# attinier85-motherboard-mk-3_0.net
KiCad netlist of a schematic drawn in EAGLE
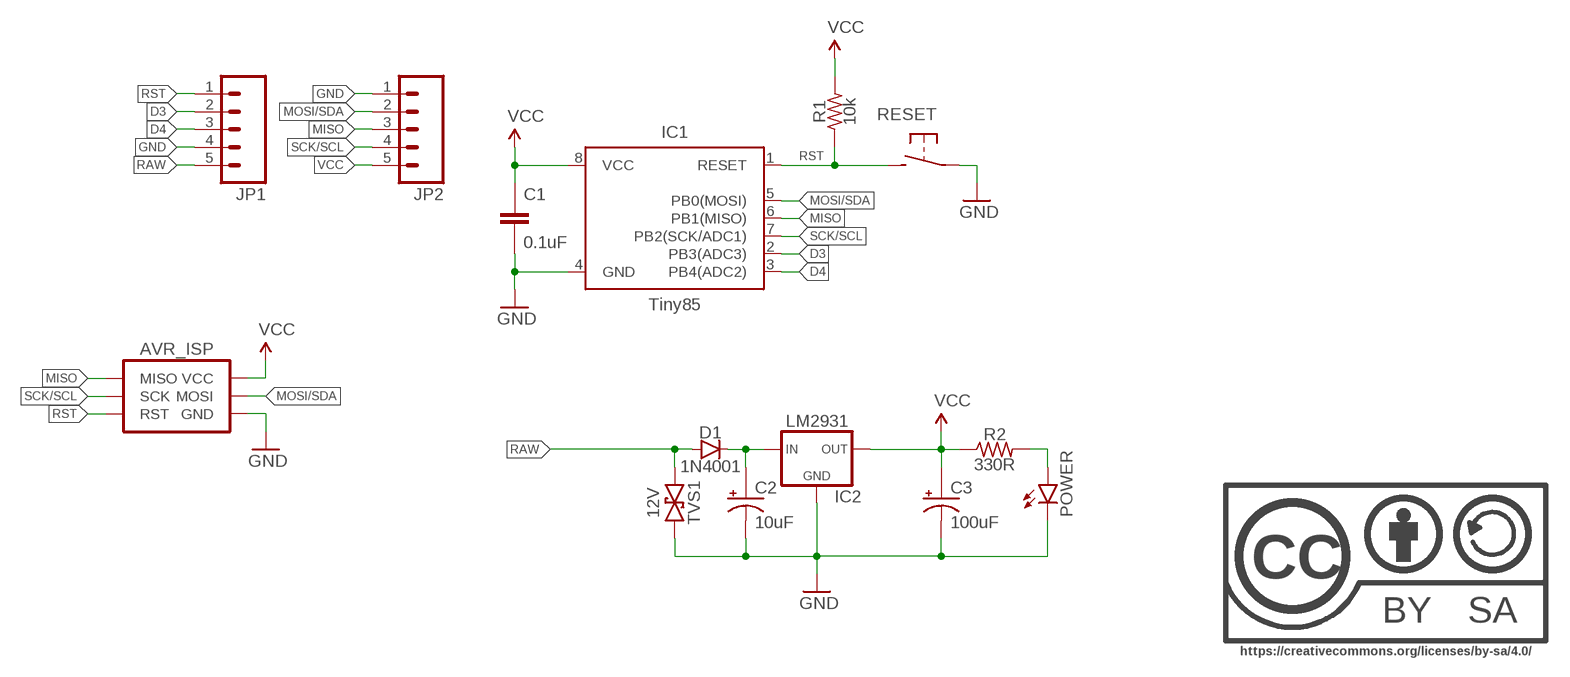
[diagram p0: schematic, sheet 1]

(export (version "E")
  (design (tool "Eeschema 10.0.6"))
  (components
    (comp (ref "AVR_ISP")
      (value "AVR_SPI_PRG_6PTH")
      (footprint "eagle-import:2X3")
      (libsource (lib "eagle-import") (part "AVR_SPI_PRG_6PTH"))
    )
    (comp (ref "C1")
      (value "0.1uF")
      (footprint "eagle-import:C025-024X044")
      (libsource (lib "eagle-import") (part "CAPACITOR-CERAMIC025-024X044"))
    )
    (comp (ref "C2")
      (value "10uF")
      (footprint "eagle-import:E2,5-5")
      (libsource (lib "eagle-import") (part "CAPACITOR-POLARIZEDE2.5-5"))
    )
    (comp (ref "C3")
      (value "100uF")
      (footprint "eagle-import:E2,5-5")
      (libsource (lib "eagle-import") (part "CAPACITOR-POLARIZEDE2.5-5"))
    )
    (comp (ref "D1")
      (value "1N4001")
      (footprint "eagle-import:DIODE-10.16MM")
      (libsource (lib "eagle-import") (part "DIODEPTH-10.68MM"))
    )
    (comp (ref "IC1")
      (value "Tiny85")
      (footprint "eagle-import:DIP08")
      (libsource (lib "eagle-import") (part "ATTINY45TINY85-20-DIP"))
    )
    (comp (ref "IC2")
      (value "LM2931")
      (footprint "eagle-import:TO-92-AMMO")
      (libsource (lib "eagle-import") (part "V_REG_78XXTO-92-INLINE"))
    )
    (comp (ref "JP1")
      (value "M05PTH")
      (footprint "eagle-import:1X05")
      (libsource (lib "eagle-import") (part "M05PTH"))
    )
    (comp (ref "JP2")
      (value "M05PTH")
      (footprint "eagle-import:1X05")
      (libsource (lib "eagle-import") (part "M05PTH"))
    )
    (comp (ref "POWER")
      (value "LED3MM-LESS")
      (footprint "eagle-import:LED3MM-LESSSILK")
      (libsource (lib "eagle-import") (part "LED3MM-LESS"))
    )
    (comp (ref "R1")
      (value "10k")
      (footprint "eagle-import:RESISTOR-AXIAL-PTH-7.62MM")
      (libsource (lib "eagle-import") (part "RESISTORPTH-AXIAL-7.62MM"))
    )
    (comp (ref "R2")
      (value "330R")
      (footprint "eagle-import:RESISTOR-AXIAL-PTH-7.62MM")
      (libsource (lib "eagle-import") (part "RESISTORPTH-AXIAL-7.62MM"))
    )
    (comp (ref "RESET")
      (value "DTS-6MM")
      (footprint "eagle-import:DTS-3-SMALL-PADS")
      (libsource (lib "eagle-import") (part "SPST-NO-TACT3MM-PTH-SMALL-PADS"))
    )
    (comp (ref "TVS1")
      (value "12V")
      (footprint "eagle-import:DO-41-TVS")
      (libsource (lib "eagle-import") (part "TVSDO-41-TVS-BIDIRECTIONAL"))
    )
    (comp (ref "U$1")
      (value "CC-BY-SA-4.0NO-URL")
      (footprint "eagle-import:CC-BY-SA-4.0-NO-URL")
      (libsource (lib "eagle-import") (part "CC-BY-SA-4.0NO-URL"))
    )
  )
  (nets
    (net (code "1") (name "D3") (class "Default")
      (node (ref "IC1") (pin "2") (pinfunction "PB3(ADC3)_2") (pintype "bidirectional"))
      (node (ref "JP1") (pin "2") (pinfunction "2_2") (pintype "passive"))
    )
    (net (code "2") (name "D4") (class "Default")
      (node (ref "IC1") (pin "3") (pinfunction "PB4(ADC2)_3") (pintype "bidirectional"))
      (node (ref "JP1") (pin "3") (pinfunction "3_3") (pintype "passive"))
    )
    (net (code "3") (name "GND") (class "Default")
      (node (ref "AVR_ISP") (pin "6") (pinfunction "GND_6") (pintype "passive"))
      (node (ref "C1") (pin "2") (pinfunction "2_2") (pintype "passive"))
      (node (ref "C2") (pin "-") (pinfunction "-_-") (pintype "passive"))
      (node (ref "C3") (pin "-") (pinfunction "-_-") (pintype "passive"))
      (node (ref "IC1") (pin "4") (pinfunction "GND_4") (pintype "bidirectional"))
      (node (ref "IC2") (pin "2") (pinfunction "GND_2") (pintype "bidirectional"))
      (node (ref "JP1") (pin "4") (pinfunction "4_4") (pintype "passive"))
      (node (ref "JP2") (pin "1") (pinfunction "1_1") (pintype "passive"))
      (node (ref "POWER") (pin "K") (pinfunction "C_K") (pintype "passive"))
      (node (ref "RESET") (pin "1") (pinfunction "1_1") (pintype "passive"))
      (node (ref "TVS1") (pin "P$2") (pinfunction "2_P$2") (pintype "passive"))
    )
    (net (code "4") (name "MISO") (class "Default")
      (node (ref "AVR_ISP") (pin "1") (pinfunction "MISO_1") (pintype "passive"))
      (node (ref "IC1") (pin "6") (pinfunction "PB1(MISO)_6") (pintype "bidirectional"))
      (node (ref "JP2") (pin "3") (pinfunction "3_3") (pintype "passive"))
    )
    (net (code "5") (name "MOSI{slash}SDA") (class "Default")
      (node (ref "AVR_ISP") (pin "4") (pinfunction "MOSI_4") (pintype "passive"))
      (node (ref "IC1") (pin "5") (pinfunction "PB0(MOSI)_5") (pintype "bidirectional"))
      (node (ref "JP2") (pin "2") (pinfunction "2_2") (pintype "passive"))
    )
    (net (code "6") (name "Net-(IC2-IN)") (class "Default")
      (node (ref "C2") (pin "+") (pinfunction "+_+") (pintype "passive"))
      (node (ref "D1") (pin "C") (pinfunction "C_C") (pintype "passive"))
      (node (ref "IC2") (pin "1") (pinfunction "IN_1") (pintype "bidirectional"))
    )
    (net (code "7") (name "Net-(R2-2)") (class "Default")
      (node (ref "POWER") (pin "A") (pinfunction "A_A") (pintype "passive"))
      (node (ref "R2") (pin "P$2") (pinfunction "2_P$2") (pintype "passive"))
    )
    (net (code "8") (name "RAW") (class "Default")
      (node (ref "D1") (pin "A") (pinfunction "A_A") (pintype "passive"))
      (node (ref "JP1") (pin "5") (pinfunction "5_5") (pintype "passive"))
      (node (ref "TVS1") (pin "P$1") (pinfunction "1_P$1") (pintype "passive"))
    )
    (net (code "9") (name "RST") (class "Default")
      (node (ref "AVR_ISP") (pin "5") (pinfunction "RST_5") (pintype "passive"))
      (node (ref "IC1") (pin "1") (pinfunction "RESET_1") (pintype "bidirectional"))
      (node (ref "JP1") (pin "1") (pinfunction "1_1") (pintype "passive"))
      (node (ref "R1") (pin "P$1") (pinfunction "1_P$1") (pintype "passive"))
      (node (ref "RESET") (pin "2") (pinfunction "2_2") (pintype "passive"))
    )
    (net (code "10") (name "SCK{slash}SCL") (class "Default")
      (node (ref "AVR_ISP") (pin "3") (pinfunction "SCK_3") (pintype "passive"))
      (node (ref "IC1") (pin "7") (pinfunction "PB2(SCK/ADC1)_7") (pintype "bidirectional"))
      (node (ref "JP2") (pin "4") (pinfunction "4_4") (pintype "passive"))
    )
    (net (code "11") (name "VCC") (class "Default")
      (node (ref "AVR_ISP") (pin "2") (pinfunction "VCC_2") (pintype "passive"))
      (node (ref "C1") (pin "1") (pinfunction "1_1") (pintype "passive"))
      (node (ref "C3") (pin "+") (pinfunction "+_+") (pintype "passive"))
      (node (ref "IC1") (pin "8") (pinfunction "VCC_8") (pintype "bidirectional"))
      (node (ref "IC2") (pin "3") (pinfunction "OUT_3") (pintype "bidirectional"))
      (node (ref "JP2") (pin "5") (pinfunction "5_5") (pintype "passive"))
      (node (ref "R1") (pin "P$2") (pinfunction "2_P$2") (pintype "passive"))
      (node (ref "R2") (pin "P$1") (pinfunction "1_P$1") (pintype "passive"))
    )
  )
)
